# LED_Driver_AREM-90C0.net
KiCad netlist of a schematic drawn in Altium Designer
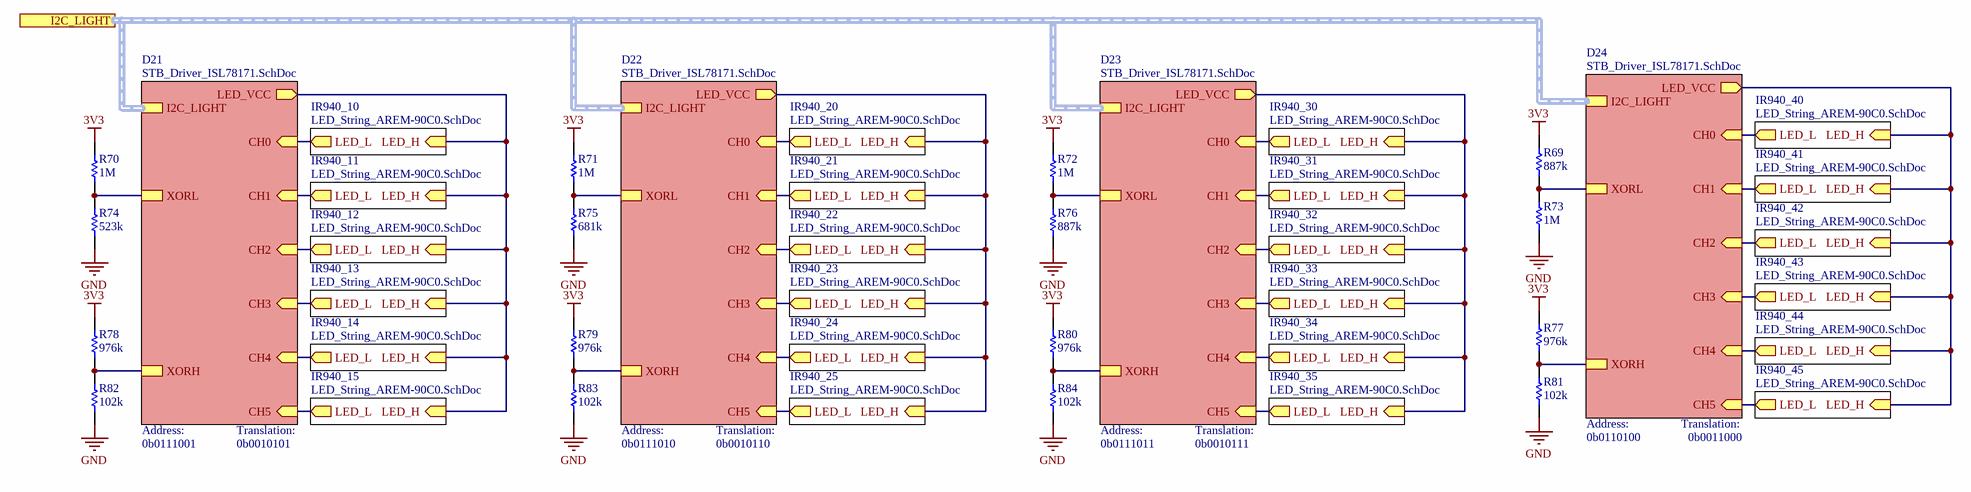
[diagram p0: LED_Driver_AREM-90C0.SchDoc]

(export (version "E")
  (design (tool "Eeschema 10.0.6"))
  (components
    (comp (ref "R69")
      (value "887k")
      (footprint "RESC1005X40X25LL05T10")
      (fields
        (field (name "PART NUMBER") "RC0402FR-07887KL")
        (field (name "MANUFACTURER") "Yageo / Phycomp")
        (field (name "TOLERANCE") "1%")
      )
      (libsource (lib "Altium Content Vault") (part "RES"))
    )
    (comp (ref "R70")
      (value "1M")
      (footprint "RESC1005X40X25LL05T05")
      (description "Chip Resistor, 1 MOhm, +/- 1%, 100 mW, -55 to 155 degC, 0402 (1005 Metric), RoHS, Tape and Reel")
      (fields (field (name "PARTNUMBER") "ERJ-2RKF1004X") (field (name "TOLERANCE") "1%"))
      (libsource (lib "Altium Content Vault") (part "RES-2"))
    )
    (comp (ref "R71")
      (value "1M")
      (footprint "RESC1005X40X25LL05T05")
      (description "Chip Resistor, 1 MOhm, +/- 1%, 100 mW, -55 to 155 degC, 0402 (1005 Metric), RoHS, Tape and Reel")
      (fields (field (name "PARTNUMBER") "ERJ-2RKF1004X") (field (name "TOLERANCE") "1%"))
      (libsource (lib "Altium Content Vault") (part "RES-2"))
    )
    (comp (ref "R72")
      (value "1M")
      (footprint "RESC1005X40X25LL05T05")
      (description "Chip Resistor, 1 MOhm, +/- 1%, 100 mW, -55 to 155 degC, 0402 (1005 Metric), RoHS, Tape and Reel")
      (fields (field (name "PARTNUMBER") "ERJ-2RKF1004X") (field (name "TOLERANCE") "1%"))
      (libsource (lib "Altium Content Vault") (part "RES-2"))
    )
    (comp (ref "R73")
      (value "1M")
      (footprint "RESC1005X40X25LL05T05")
      (description "Chip Resistor, 1 MOhm, +/- 1%, 100 mW, -55 to 155 degC, 0402 (1005 Metric), RoHS, Tape and Reel")
      (fields (field (name "PARTNUMBER") "ERJ-2RKF1004X") (field (name "TOLERANCE") "1%"))
      (libsource (lib "Altium Content Vault") (part "RES-2"))
    )
    (comp (ref "R74")
      (value "523k")
      (footprint "RESC1005X40X25LL05T05")
      (fields
        (field (name "MANUFACTURER") "Panasonic")
        (field (name "PART NUMBER") "ERJ-2RKF5233X")
        (field (name "TOLERANCE") "1%")
      )
      (libsource (lib "Altium Content Vault") (part "RES"))
    )
    (comp (ref "R75")
      (value "681k")
      (footprint "RESC1005X40X25LL05T05")
      (fields
        (field (name "MANUFACTURER") "Panasonic")
        (field (name "PART NUMBER") "ERJ-2RKF6813X")
        (field (name "TOLERANCE") "1%")
      )
      (libsource (lib "Altium Content Vault") (part "RES"))
    )
    (comp (ref "R76")
      (value "887k")
      (footprint "RESC1005X40X25LL05T10")
      (fields
        (field (name "PART NUMBER") "RC0402FR-07887KL")
        (field (name "MANUFACTURER") "Yageo / Phycomp")
        (field (name "TOLERANCE") "1%")
      )
      (libsource (lib "Altium Content Vault") (part "RES"))
    )
    (comp (ref "R77")
      (value "976k")
      (footprint "RESC1005X40X25LL05T05")
      (fields
        (field (name "MANUFACTURER") "Panasonic")
        (field (name "PART NUMBER") "ERJ-2RKF9763X")
        (field (name "TOLERANCE") "1%")
      )
      (libsource (lib "Altium Content Vault") (part "RES"))
    )
    (comp (ref "R78")
      (value "976k")
      (footprint "RESC1005X40X25LL05T05")
      (fields
        (field (name "MANUFACTURER") "Panasonic")
        (field (name "PART NUMBER") "ERJ-2RKF9763X")
        (field (name "TOLERANCE") "1%")
      )
      (libsource (lib "Altium Content Vault") (part "RES"))
    )
    (comp (ref "R79")
      (value "976k")
      (footprint "RESC1005X40X25LL05T05")
      (fields
        (field (name "MANUFACTURER") "Panasonic")
        (field (name "PART NUMBER") "ERJ-2RKF9763X")
        (field (name "TOLERANCE") "1%")
      )
      (libsource (lib "Altium Content Vault") (part "RES"))
    )
    (comp (ref "R80")
      (value "976k")
      (footprint "RESC1005X40X25LL05T05")
      (fields
        (field (name "MANUFACTURER") "Panasonic")
        (field (name "PART NUMBER") "ERJ-2RKF9763X")
        (field (name "TOLERANCE") "1%")
      )
      (libsource (lib "Altium Content Vault") (part "RES"))
    )
    (comp (ref "R81")
      (value "102k")
      (footprint "RESC1005X40X25LL05T05")
      (fields
        (field (name "MANUFACTURER") "Panasonic")
        (field (name "PART NUMBER") "ERJ-2RKF1023X")
        (field (name "TOLERANCE") "1%")
      )
      (libsource (lib "Altium Content Vault") (part "RES"))
    )
    (comp (ref "R82")
      (value "102k")
      (footprint "RESC1005X40X25LL05T05")
      (fields
        (field (name "MANUFACTURER") "Panasonic")
        (field (name "PART NUMBER") "ERJ-2RKF1023X")
        (field (name "TOLERANCE") "1%")
      )
      (libsource (lib "Altium Content Vault") (part "RES"))
    )
    (comp (ref "R83")
      (value "102k")
      (footprint "RESC1005X40X25LL05T05")
      (fields
        (field (name "MANUFACTURER") "Panasonic")
        (field (name "PART NUMBER") "ERJ-2RKF1023X")
        (field (name "TOLERANCE") "1%")
      )
      (libsource (lib "Altium Content Vault") (part "RES"))
    )
    (comp (ref "R84")
      (value "102k")
      (footprint "RESC1005X40X25LL05T05")
      (fields
        (field (name "MANUFACTURER") "Panasonic")
        (field (name "PART NUMBER") "ERJ-2RKF1023X")
        (field (name "TOLERANCE") "1%")
      )
      (libsource (lib "Altium Content Vault") (part "RES"))
    )
  )
  (nets
    (net (code "32") (name "/XORH") (class "Default")
      (node (ref "R77") (pin "1") (pinfunction "1_1") (pintype "passive"))
      (node (ref "R81") (pin "2") (pinfunction "2_2") (pintype "passive"))
    )
    (net (code "33") (name "/XORH_1") (class "Default")
      (node (ref "R79") (pin "1") (pinfunction "1_1") (pintype "passive"))
      (node (ref "R83") (pin "2") (pinfunction "2_2") (pintype "passive"))
    )
    (net (code "34") (name "/XORH_2") (class "Default")
      (node (ref "R78") (pin "1") (pinfunction "1_1") (pintype "passive"))
      (node (ref "R82") (pin "2") (pinfunction "2_2") (pintype "passive"))
    )
    (net (code "35") (name "/XORH_3") (class "Default")
      (node (ref "R80") (pin "1") (pinfunction "1_1") (pintype "passive"))
      (node (ref "R84") (pin "2") (pinfunction "2_2") (pintype "passive"))
    )
    (net (code "36") (name "/XORL") (class "Default")
      (node (ref "R69") (pin "1") (pinfunction "1_1") (pintype "passive"))
      (node (ref "R73") (pin "2") (pinfunction "2_2") (pintype "passive"))
    )
    (net (code "37") (name "/XORL_1") (class "Default")
      (node (ref "R71") (pin "1") (pinfunction "1_1") (pintype "passive"))
      (node (ref "R75") (pin "2") (pinfunction "2_2") (pintype "passive"))
    )
    (net (code "38") (name "/XORL_2") (class "Default")
      (node (ref "R70") (pin "1") (pinfunction "1_1") (pintype "passive"))
      (node (ref "R74") (pin "2") (pinfunction "2_2") (pintype "passive"))
    )
    (net (code "39") (name "/XORL_3") (class "Default")
      (node (ref "R72") (pin "1") (pinfunction "1_1") (pintype "passive"))
      (node (ref "R76") (pin "2") (pinfunction "2_2") (pintype "passive"))
    )
    (net (code "40") (name "3V3") (class "Default")
      (node (ref "R69") (pin "2") (pinfunction "2_2") (pintype "passive"))
      (node (ref "R70") (pin "2") (pinfunction "2_2") (pintype "passive"))
      (node (ref "R71") (pin "2") (pinfunction "2_2") (pintype "passive"))
      (node (ref "R72") (pin "2") (pinfunction "2_2") (pintype "passive"))
      (node (ref "R77") (pin "2") (pinfunction "2_2") (pintype "passive"))
      (node (ref "R78") (pin "2") (pinfunction "2_2") (pintype "passive"))
      (node (ref "R79") (pin "2") (pinfunction "2_2") (pintype "passive"))
      (node (ref "R80") (pin "2") (pinfunction "2_2") (pintype "passive"))
    )
    (net (code "41") (name "GND") (class "Default")
      (node (ref "R73") (pin "1") (pinfunction "1_1") (pintype "passive"))
      (node (ref "R74") (pin "1") (pinfunction "1_1") (pintype "passive"))
      (node (ref "R75") (pin "1") (pinfunction "1_1") (pintype "passive"))
      (node (ref "R76") (pin "1") (pinfunction "1_1") (pintype "passive"))
      (node (ref "R81") (pin "1") (pinfunction "1_1") (pintype "passive"))
      (node (ref "R82") (pin "1") (pinfunction "1_1") (pintype "passive"))
      (node (ref "R83") (pin "1") (pinfunction "1_1") (pintype "passive"))
      (node (ref "R84") (pin "1") (pinfunction "1_1") (pintype "passive"))
    )
  )
)
